# MQTTUSBSwitch.net
KiCad netlist of a schematic drawn in EAGLE
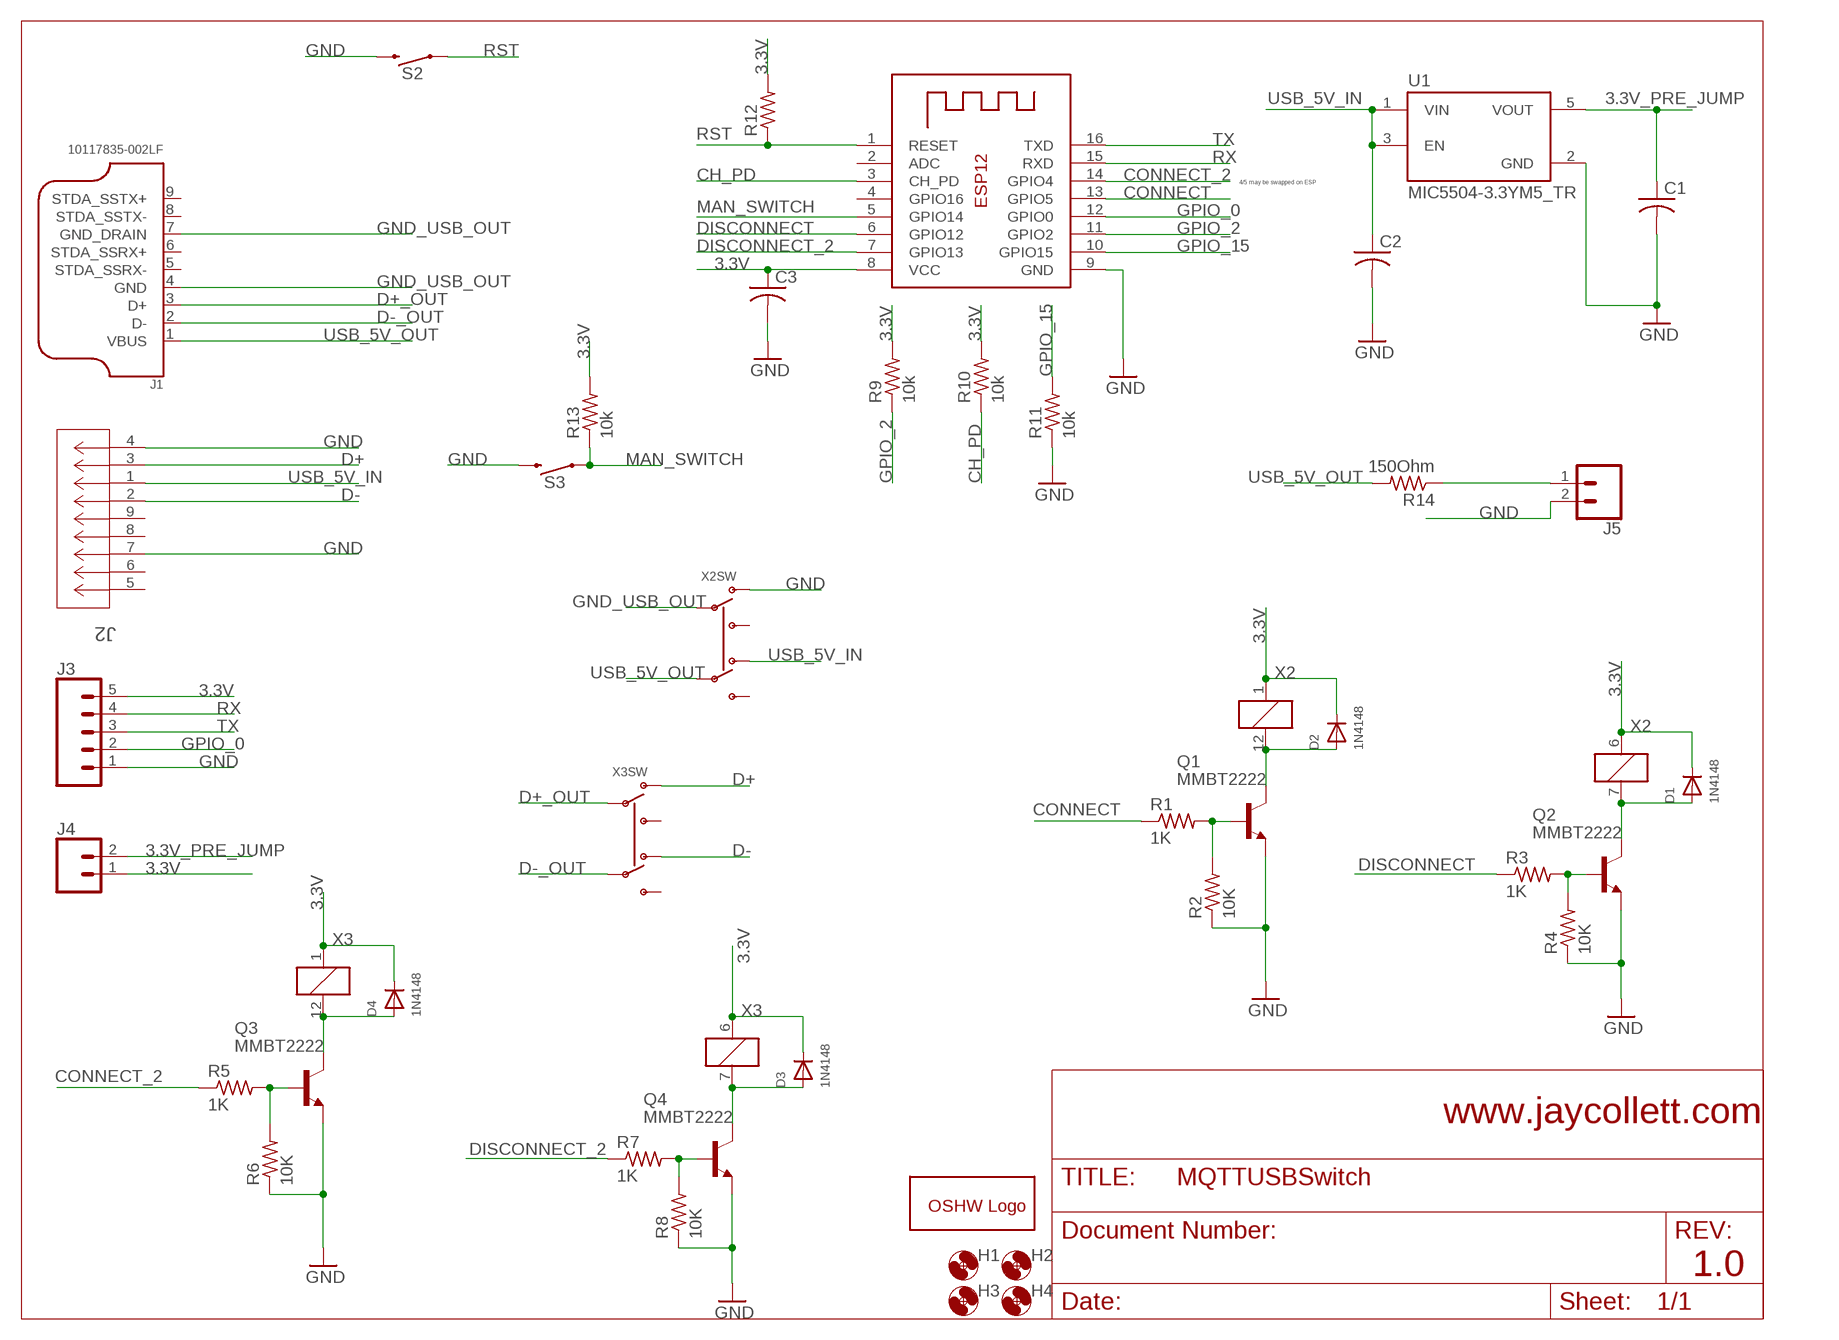
[diagram p0: schematic, sheet 1]

(export (version "E")
  (design (tool "Eeschema 10.0.6"))
  (components
    (comp (ref "C1")
      (value "C-USC0805")
      (footprint "eagle-import:C0805")
      (libsource (lib "eagle-import") (part "C-USC0805"))
    )
    (comp (ref "C2")
      (value "C-USC0805")
      (footprint "eagle-import:C0805")
      (libsource (lib "eagle-import") (part "C-USC0805"))
    )
    (comp (ref "C3")
      (value "C-USC0805")
      (footprint "eagle-import:C0805")
      (libsource (lib "eagle-import") (part "C-USC0805"))
    )
    (comp (ref "D1")
      (value "1N4148")
      (footprint "eagle-import:SOD-323F")
      (libsource (lib "eagle-import") (part "DIODESOD-323F"))
    )
    (comp (ref "D2")
      (value "1N4148")
      (footprint "eagle-import:SOD-323F")
      (libsource (lib "eagle-import") (part "DIODESOD-323F"))
    )
    (comp (ref "D3")
      (value "1N4148")
      (footprint "eagle-import:SOD-323F")
      (libsource (lib "eagle-import") (part "DIODESOD-323F"))
    )
    (comp (ref "D4")
      (value "1N4148")
      (footprint "eagle-import:SOD-323F")
      (libsource (lib "eagle-import") (part "DIODESOD-323F"))
    )
    (comp (ref "GOLD_ORB_SM1")
      (value "OSHWLOGOLOGO5MM")
      (footprint "eagle-import:OSHW_5MM")
      (libsource (lib "eagle-import") (part "OSHWLOGOLOGO5MM"))
    )
    (comp (ref "H1")
      (value "MOUNT-HOLE3.0")
      (footprint "eagle-import:3,0")
      (libsource (lib "eagle-import") (part "MOUNT-HOLE3.0"))
    )
    (comp (ref "H2")
      (value "MOUNT-HOLE3.0")
      (footprint "eagle-import:3,0")
      (libsource (lib "eagle-import") (part "MOUNT-HOLE3.0"))
    )
    (comp (ref "H3")
      (value "MOUNT-HOLE3.0")
      (footprint "eagle-import:3,0")
      (libsource (lib "eagle-import") (part "MOUNT-HOLE3.0"))
    )
    (comp (ref "H4")
      (value "MOUNT-HOLE3.0")
      (footprint "eagle-import:3,0")
      (libsource (lib "eagle-import") (part "MOUNT-HOLE3.0"))
    )
    (comp (ref "J1")
      (value "10117835-002LF")
      (footprint "eagle-import:FCI_10117835-002LF")
      (fields (field (name "DIGI-KEY_PART_NUMBER") "609-4662-ND") (field (name "MF") "Amphenol ICC (FCI)"))
      (libsource (lib "eagle-import") (part "10117835-002LF"))
    )
    (comp (ref "J2")
      (value "GSB4211311WEU")
      (footprint "eagle-import:CONN9_1311WEU_AMP")
      (fields (field (name "COPYRIGHT") "Copyright (C) 2018 Accelerated Designs. All rights reserved"))
      (libsource (lib "eagle-import") (part "GSB4211311WEU"))
    )
    (comp (ref "J3")
      (value "CONN_05")
      (footprint "eagle-import:1X05")
      (libsource (lib "eagle-import") (part "CONN_05"))
    )
    (comp (ref "J4")
      (value "CONN_02")
      (footprint "eagle-import:1X02")
      (libsource (lib "eagle-import") (part "CONN_02"))
    )
    (comp (ref "J5")
      (value "CONN_02")
      (footprint "eagle-import:1X02")
      (libsource (lib "eagle-import") (part "CONN_02"))
    )
    (comp (ref "Q1")
      (value "MMBT2222")
      (footprint "eagle-import:SOT23-BEC")
      (fields (field (name "MF") "ON Semiconductor"))
      (libsource (lib "eagle-import") (part "MMBT2222"))
    )
    (comp (ref "Q2")
      (value "MMBT2222")
      (footprint "eagle-import:SOT23-BEC")
      (fields (field (name "MF") "ON Semiconductor"))
      (libsource (lib "eagle-import") (part "MMBT2222"))
    )
    (comp (ref "Q3")
      (value "MMBT2222")
      (footprint "eagle-import:SOT23-BEC")
      (fields (field (name "MF") "ON Semiconductor"))
      (libsource (lib "eagle-import") (part "MMBT2222"))
    )
    (comp (ref "Q4")
      (value "MMBT2222")
      (footprint "eagle-import:SOT23-BEC")
      (fields (field (name "MF") "ON Semiconductor"))
      (libsource (lib "eagle-import") (part "MMBT2222"))
    )
    (comp (ref "R1")
      (value "1K")
      (footprint "eagle-import:M0805")
      (libsource (lib "eagle-import") (part "R-US_M0805"))
    )
    (comp (ref "R2")
      (value "10K")
      (footprint "eagle-import:M0805")
      (libsource (lib "eagle-import") (part "R-US_M0805"))
    )
    (comp (ref "R3")
      (value "1K")
      (footprint "eagle-import:M0805")
      (libsource (lib "eagle-import") (part "R-US_M0805"))
    )
    (comp (ref "R4")
      (value "10K")
      (footprint "eagle-import:M0805")
      (libsource (lib "eagle-import") (part "R-US_M0805"))
    )
    (comp (ref "R5")
      (value "1K")
      (footprint "eagle-import:M0805")
      (libsource (lib "eagle-import") (part "R-US_M0805"))
    )
    (comp (ref "R6")
      (value "10K")
      (footprint "eagle-import:M0805")
      (libsource (lib "eagle-import") (part "R-US_M0805"))
    )
    (comp (ref "R7")
      (value "1K")
      (footprint "eagle-import:M0805")
      (libsource (lib "eagle-import") (part "R-US_M0805"))
    )
    (comp (ref "R8")
      (value "10K")
      (footprint "eagle-import:M0805")
      (libsource (lib "eagle-import") (part "R-US_M0805"))
    )
    (comp (ref "R9")
      (value "10k")
      (footprint "eagle-import:R0805")
      (libsource (lib "eagle-import") (part "R-US_R0805"))
    )
    (comp (ref "R10")
      (value "10k")
      (footprint "eagle-import:R0805")
      (libsource (lib "eagle-import") (part "R-US_R0805"))
    )
    (comp (ref "R11")
      (value "10k")
      (footprint "eagle-import:R0805")
      (libsource (lib "eagle-import") (part "R-US_R0805"))
    )
    (comp (ref "R12")
      (value "R-US_R0805")
      (footprint "eagle-import:R0805")
      (libsource (lib "eagle-import") (part "R-US_R0805"))
    )
    (comp (ref "R13")
      (value "10k")
      (footprint "eagle-import:R0805")
      (libsource (lib "eagle-import") (part "R-US_R0805"))
    )
    (comp (ref "R14")
      (value "150Ohm")
      (footprint "eagle-import:R0805")
      (libsource (lib "eagle-import") (part "R-US_R0805"))
    )
    (comp (ref "S2")
      (value "MOMENTARY-SWITCH-SPST-PTH-6.0MM-KIT")
      (footprint "eagle-import:TACTILE_SWITCH_PTH_6.0MM_KIT")
      (libsource (lib "eagle-import") (part "MOMENTARY-SWITCH-SPST-PTH-6.0MM-KIT"))
    )
    (comp (ref "S3")
      (value "MOMENTARY-SWITCH-SPST-PTH-6.0MM-KIT")
      (footprint "eagle-import:TACTILE_SWITCH_PTH_6.0MM_KIT")
      (libsource (lib "eagle-import") (part "MOMENTARY-SWITCH-SPST-PTH-6.0MM-KIT"))
    )
    (comp (ref "U1")
      (value "MIC5504-3.3YM5_TR")
      (footprint "eagle-import:SOT95P280X145-5N")
      (fields (field (name "MF") "Microchip") (field (name "MP") "MIC5504-3.3YM5 TR"))
      (libsource (lib "eagle-import") (part "MIC5504-3.3YM5_TR"))
    )
    (comp (ref "X1")
      (value "ESP-12")
      (footprint "eagle-import:ESP-12")
      (libsource (lib "eagle-import") (part "ESP-12"))
    )
    (comp (ref "X2")
      (value "MICROBUILDER_RELAY_LATCHINGEE2NUH")
      (footprint "eagle-import:MICROBUILDER_RELAY_EE2_LATCH")
      (libsource (lib "eagle-import") (part "MICROBUILDER_RELAY_LATCHINGEE2NUH"))
    )
    (comp (ref "X3")
      (value "MICROBUILDER_RELAY_LATCHINGEE2NUH")
      (footprint "eagle-import:MICROBUILDER_RELAY_EE2_LATCH")
      (libsource (lib "eagle-import") (part "MICROBUILDER_RELAY_LATCHINGEE2NUH"))
    )
  )
  (nets
    (net (code "1") (name "/3.3V") (class "Default")
      (node (ref "C3") (pin "1") (pinfunction "1_1") (pintype "passive"))
      (node (ref "D1") (pin "C") (pinfunction "C_C") (pintype "passive"))
      (node (ref "D2") (pin "C") (pinfunction "C_C") (pintype "passive"))
      (node (ref "D3") (pin "C") (pinfunction "C_C") (pintype "passive"))
      (node (ref "D4") (pin "C") (pinfunction "C_C") (pintype "passive"))
      (node (ref "J3") (pin "5") (pinfunction "5_5") (pintype "passive"))
      (node (ref "J4") (pin "1") (pinfunction "1_1") (pintype "passive"))
      (node (ref "R10") (pin "2") (pinfunction "2_2") (pintype "passive"))
      (node (ref "R12") (pin "2") (pinfunction "2_2") (pintype "passive"))
      (node (ref "R13") (pin "2") (pinfunction "2_2") (pintype "passive"))
      (node (ref "R9") (pin "2") (pinfunction "2_2") (pintype "passive"))
      (node (ref "X1") (pin "8") (pinfunction "VCC_8") (pintype "power_in"))
      (node (ref "X2") (pin "1") (pinfunction "1_1") (pintype "passive"))
      (node (ref "X2") (pin "6") (pinfunction "1_6") (pintype "passive"))
      (node (ref "X3") (pin "1") (pinfunction "1_1") (pintype "passive"))
      (node (ref "X3") (pin "6") (pinfunction "1_6") (pintype "passive"))
    )
    (net (code "2") (name "/3.3V_PRE_JUMP") (class "Default")
      (node (ref "C1") (pin "1") (pinfunction "1_1") (pintype "passive"))
      (node (ref "J4") (pin "2") (pinfunction "2_2") (pintype "passive"))
      (node (ref "U1") (pin "5") (pinfunction "VOUT_5") (pintype "output"))
    )
    (net (code "3") (name "/CH_PD") (class "Default")
      (node (ref "R10") (pin "1") (pinfunction "1_1") (pintype "passive"))
      (node (ref "X1") (pin "3") (pinfunction "CH_PD_3") (pintype "input"))
    )
    (net (code "4") (name "/CONNECT") (class "Default")
      (node (ref "R1") (pin "1") (pinfunction "1_1") (pintype "passive"))
      (node (ref "X1") (pin "13") (pinfunction "GPIO5_13") (pintype "bidirectional"))
    )
    (net (code "5") (name "/CONNECT_2") (class "Default")
      (node (ref "R5") (pin "1") (pinfunction "1_1") (pintype "passive"))
      (node (ref "X1") (pin "14") (pinfunction "GPIO4_14") (pintype "bidirectional"))
    )
    (net (code "6") (name "/D+") (class "Default")
      (node (ref "J2") (pin "3") (pinfunction "3_3") (pintype "passive"))
      (node (ref "X3") (pin "10") (pinfunction "O1_10") (pintype "passive"))
    )
    (net (code "7") (name "/D+_OUT") (class "Default")
      (node (ref "J1") (pin "3") (pinfunction "D+_3") (pintype "bidirectional"))
      (node (ref "X3") (pin "9") (pinfunction "P1_9") (pintype "passive"))
    )
    (net (code "8") (name "/D-") (class "Default")
      (node (ref "J2") (pin "2") (pinfunction "2_2") (pintype "passive"))
      (node (ref "X3") (pin "3") (pinfunction "O2_3") (pintype "passive"))
    )
    (net (code "9") (name "/D-_OUT") (class "Default")
      (node (ref "J1") (pin "2") (pinfunction "D-_2") (pintype "bidirectional"))
      (node (ref "X3") (pin "4") (pinfunction "P2_4") (pintype "passive"))
    )
    (net (code "10") (name "/DISCONNECT") (class "Default")
      (node (ref "R3") (pin "1") (pinfunction "1_1") (pintype "passive"))
      (node (ref "X1") (pin "6") (pinfunction "GPIO12_6") (pintype "bidirectional"))
    )
    (net (code "11") (name "/DISCONNECT_2") (class "Default")
      (node (ref "R7") (pin "1") (pinfunction "1_1") (pintype "passive"))
      (node (ref "X1") (pin "7") (pinfunction "GPIO13_7") (pintype "bidirectional"))
    )
    (net (code "12") (name "/GND_USB_OUT") (class "Default")
      (node (ref "J1") (pin "4") (pinfunction "GND_4") (pintype "power_in"))
      (node (ref "J1") (pin "7") (pinfunction "GND_DRAIN_7") (pintype "power_in"))
      (node (ref "X2") (pin "9") (pinfunction "P1_9") (pintype "passive"))
    )
    (net (code "13") (name "/GPIO_0") (class "Default")
      (node (ref "J3") (pin "2") (pinfunction "2_2") (pintype "passive"))
      (node (ref "X1") (pin "12") (pinfunction "GPIO0_12") (pintype "bidirectional"))
    )
    (net (code "14") (name "/GPIO_2") (class "Default")
      (node (ref "R9") (pin "1") (pinfunction "1_1") (pintype "passive"))
      (node (ref "X1") (pin "11") (pinfunction "GPIO2_11") (pintype "bidirectional"))
    )
    (net (code "15") (name "/GPIO_15") (class "Default")
      (node (ref "R11") (pin "2") (pinfunction "2_2") (pintype "passive"))
      (node (ref "X1") (pin "10") (pinfunction "GPIO15_10") (pintype "bidirectional"))
    )
    (net (code "16") (name "/MAN_SWITCH") (class "Default")
      (node (ref "R13") (pin "1") (pinfunction "1_1") (pintype "passive"))
      (node (ref "S3") (pin "1") (pinfunction "1_1") (pintype "passive"))
      (node (ref "X1") (pin "5") (pinfunction "GPIO14_5") (pintype "bidirectional"))
    )
    (net (code "17") (name "/RST") (class "Default")
      (node (ref "R12") (pin "1") (pinfunction "1_1") (pintype "passive"))
      (node (ref "S2") (pin "1") (pinfunction "1_1") (pintype "passive"))
      (node (ref "X1") (pin "1") (pinfunction "RESET_1") (pintype "input"))
    )
    (net (code "18") (name "/RX") (class "Default")
      (node (ref "J3") (pin "4") (pinfunction "4_4") (pintype "passive"))
      (node (ref "X1") (pin "15") (pinfunction "RXD_15") (pintype "input"))
    )
    (net (code "19") (name "/TX") (class "Default")
      (node (ref "J3") (pin "3") (pinfunction "3_3") (pintype "passive"))
      (node (ref "X1") (pin "16") (pinfunction "TXD_16") (pintype "output"))
    )
    (net (code "20") (name "/USB_5V_IN") (class "Default")
      (node (ref "C2") (pin "1") (pinfunction "1_1") (pintype "passive"))
      (node (ref "J2") (pin "1") (pinfunction "1_1") (pintype "passive"))
      (node (ref "U1") (pin "1") (pinfunction "VIN_1") (pintype "input"))
      (node (ref "U1") (pin "3") (pinfunction "EN_3") (pintype "input"))
      (node (ref "X2") (pin "3") (pinfunction "O2_3") (pintype "passive"))
    )
    (net (code "21") (name "/USB_5V_OUT") (class "Default")
      (node (ref "J1") (pin "1") (pinfunction "VBUS_1") (pintype "power_in"))
      (node (ref "R14") (pin "2") (pinfunction "2_2") (pintype "passive"))
      (node (ref "X2") (pin "4") (pinfunction "P2_4") (pintype "passive"))
    )
    (net (code "22") (name "GND") (class "Default")
      (node (ref "C1") (pin "2") (pinfunction "2_2") (pintype "passive"))
      (node (ref "C2") (pin "2") (pinfunction "2_2") (pintype "passive"))
      (node (ref "C3") (pin "2") (pinfunction "2_2") (pintype "passive"))
      (node (ref "J2") (pin "4") (pinfunction "4_4") (pintype "passive"))
      (node (ref "J2") (pin "7") (pinfunction "7_7") (pintype "passive"))
      (node (ref "J3") (pin "1") (pinfunction "1_1") (pintype "passive"))
      (node (ref "J5") (pin "2") (pinfunction "2_2") (pintype "passive"))
      (node (ref "Q1") (pin "E") (pinfunction "E_E") (pintype "passive"))
      (node (ref "Q2") (pin "E") (pinfunction "E_E") (pintype "passive"))
      (node (ref "Q3") (pin "E") (pinfunction "E_E") (pintype "passive"))
      (node (ref "Q4") (pin "E") (pinfunction "E_E") (pintype "passive"))
      (node (ref "R11") (pin "1") (pinfunction "1_1") (pintype "passive"))
      (node (ref "R2") (pin "1") (pinfunction "1_1") (pintype "passive"))
      (node (ref "R4") (pin "1") (pinfunction "1_1") (pintype "passive"))
      (node (ref "R6") (pin "1") (pinfunction "1_1") (pintype "passive"))
      (node (ref "R8") (pin "1") (pinfunction "1_1") (pintype "passive"))
      (node (ref "S2") (pin "3") (pinfunction "2_3") (pintype "passive"))
      (node (ref "S3") (pin "3") (pinfunction "2_3") (pintype "passive"))
      (node (ref "U1") (pin "2") (pinfunction "GND_2") (pintype "power_in"))
      (node (ref "X1") (pin "9") (pinfunction "GND_9") (pintype "power_in"))
      (node (ref "X2") (pin "10") (pinfunction "O1_10") (pintype "passive"))
    )
    (net (code "23") (name "Net-(J5-Pad1)") (class "Default")
      (node (ref "J5") (pin "1") (pinfunction "1_1") (pintype "passive"))
      (node (ref "R14") (pin "1") (pinfunction "1_1") (pintype "passive"))
    )
    (net (code "24") (name "Net-(Q1-PadB)") (class "Default")
      (node (ref "Q1") (pin "B") (pinfunction "B_B") (pintype "passive"))
      (node (ref "R1") (pin "2") (pinfunction "2_2") (pintype "passive"))
      (node (ref "R2") (pin "2") (pinfunction "2_2") (pintype "passive"))
    )
    (net (code "25") (name "Net-(Q2-PadB)") (class "Default")
      (node (ref "Q2") (pin "B") (pinfunction "B_B") (pintype "passive"))
      (node (ref "R3") (pin "2") (pinfunction "2_2") (pintype "passive"))
      (node (ref "R4") (pin "2") (pinfunction "2_2") (pintype "passive"))
    )
    (net (code "26") (name "Net-(Q3-PadB)") (class "Default")
      (node (ref "Q3") (pin "B") (pinfunction "B_B") (pintype "passive"))
      (node (ref "R5") (pin "2") (pinfunction "2_2") (pintype "passive"))
      (node (ref "R6") (pin "2") (pinfunction "2_2") (pintype "passive"))
    )
    (net (code "27") (name "Net-(Q4-PadB)") (class "Default")
      (node (ref "Q4") (pin "B") (pinfunction "B_B") (pintype "passive"))
      (node (ref "R7") (pin "2") (pinfunction "2_2") (pintype "passive"))
      (node (ref "R8") (pin "2") (pinfunction "2_2") (pintype "passive"))
    )
    (net (code "28") (name "Net-(X2A-2)") (class "Default")
      (node (ref "D1") (pin "A") (pinfunction "A_A") (pintype "passive"))
      (node (ref "Q2") (pin "C") (pinfunction "C_C") (pintype "passive"))
      (node (ref "X2") (pin "7") (pinfunction "2_7") (pintype "passive"))
    )
    (net (code "29") (name "Net-(X2B-2)") (class "Default")
      (node (ref "D2") (pin "A") (pinfunction "A_A") (pintype "passive"))
      (node (ref "Q1") (pin "C") (pinfunction "C_C") (pintype "passive"))
      (node (ref "X2") (pin "12") (pinfunction "2_12") (pintype "passive"))
    )
    (net (code "30") (name "Net-(X3A-2)") (class "Default")
      (node (ref "D3") (pin "A") (pinfunction "A_A") (pintype "passive"))
      (node (ref "Q4") (pin "C") (pinfunction "C_C") (pintype "passive"))
      (node (ref "X3") (pin "7") (pinfunction "2_7") (pintype "passive"))
    )
    (net (code "31") (name "Net-(X3B-2)") (class "Default")
      (node (ref "D4") (pin "A") (pinfunction "A_A") (pintype "passive"))
      (node (ref "Q3") (pin "C") (pinfunction "C_C") (pintype "passive"))
      (node (ref "X3") (pin "12") (pinfunction "2_12") (pintype "passive"))
    )
    (net (code "32") (name "unconnected-(J1-STDA_SSRX+-Pad6)") (class "Default")
      (node (ref "J1") (pin "6") (pinfunction "STDA_SSRX+_6") (pintype "bidirectional"))
    )
    (net (code "33") (name "unconnected-(J1-STDA_SSRX--Pad5)") (class "Default")
      (node (ref "J1") (pin "5") (pinfunction "STDA_SSRX-_5") (pintype "bidirectional"))
    )
    (net (code "34") (name "unconnected-(J1-STDA_SSTX+-Pad9)") (class "Default")
      (node (ref "J1") (pin "9") (pinfunction "STDA_SSTX+_9") (pintype "bidirectional"))
    )
    (net (code "35") (name "unconnected-(J1-STDA_SSTX--Pad8)") (class "Default")
      (node (ref "J1") (pin "8") (pinfunction "STDA_SSTX-_8") (pintype "bidirectional"))
    )
    (net (code "36") (name "unconnected-(J2-Pad5)") (class "Default")
      (node (ref "J2") (pin "5") (pinfunction "5_5") (pintype "passive"))
    )
    (net (code "37") (name "unconnected-(J2-Pad6)") (class "Default")
      (node (ref "J2") (pin "6") (pinfunction "6_6") (pintype "passive"))
    )
    (net (code "38") (name "unconnected-(J2-Pad8)") (class "Default")
      (node (ref "J2") (pin "8") (pinfunction "8_8") (pintype "passive"))
    )
    (net (code "39") (name "unconnected-(J2-Pad9)") (class "Default")
      (node (ref "J2") (pin "9") (pinfunction "9_9") (pintype "passive"))
    )
    (net (code "40") (name "unconnected-(X1-ADC-Pad2)") (class "Default")
      (node (ref "X1") (pin "2") (pinfunction "ADC_2") (pintype "passive"))
    )
    (net (code "41") (name "unconnected-(X1-GPIO16-Pad4)") (class "Default")
      (node (ref "X1") (pin "4") (pinfunction "GPIO16_4") (pintype "bidirectional"))
    )
    (net (code "42") (name "unconnected-(X2C-S1-Pad8)") (class "Default")
      (node (ref "X2") (pin "8") (pinfunction "S1_8") (pintype "passive"))
    )
    (net (code "43") (name "unconnected-(X2C-S2-Pad5)") (class "Default")
      (node (ref "X2") (pin "5") (pinfunction "S2_5") (pintype "passive"))
    )
    (net (code "44") (name "unconnected-(X3C-S1-Pad8)") (class "Default")
      (node (ref "X3") (pin "8") (pinfunction "S1_8") (pintype "passive"))
    )
    (net (code "45") (name "unconnected-(X3C-S2-Pad5)") (class "Default")
      (node (ref "X3") (pin "5") (pinfunction "S2_5") (pintype "passive"))
    )
  )
)
